# pcuCPU.net
KiCad netlist of a schematic drawn in Altium Designer
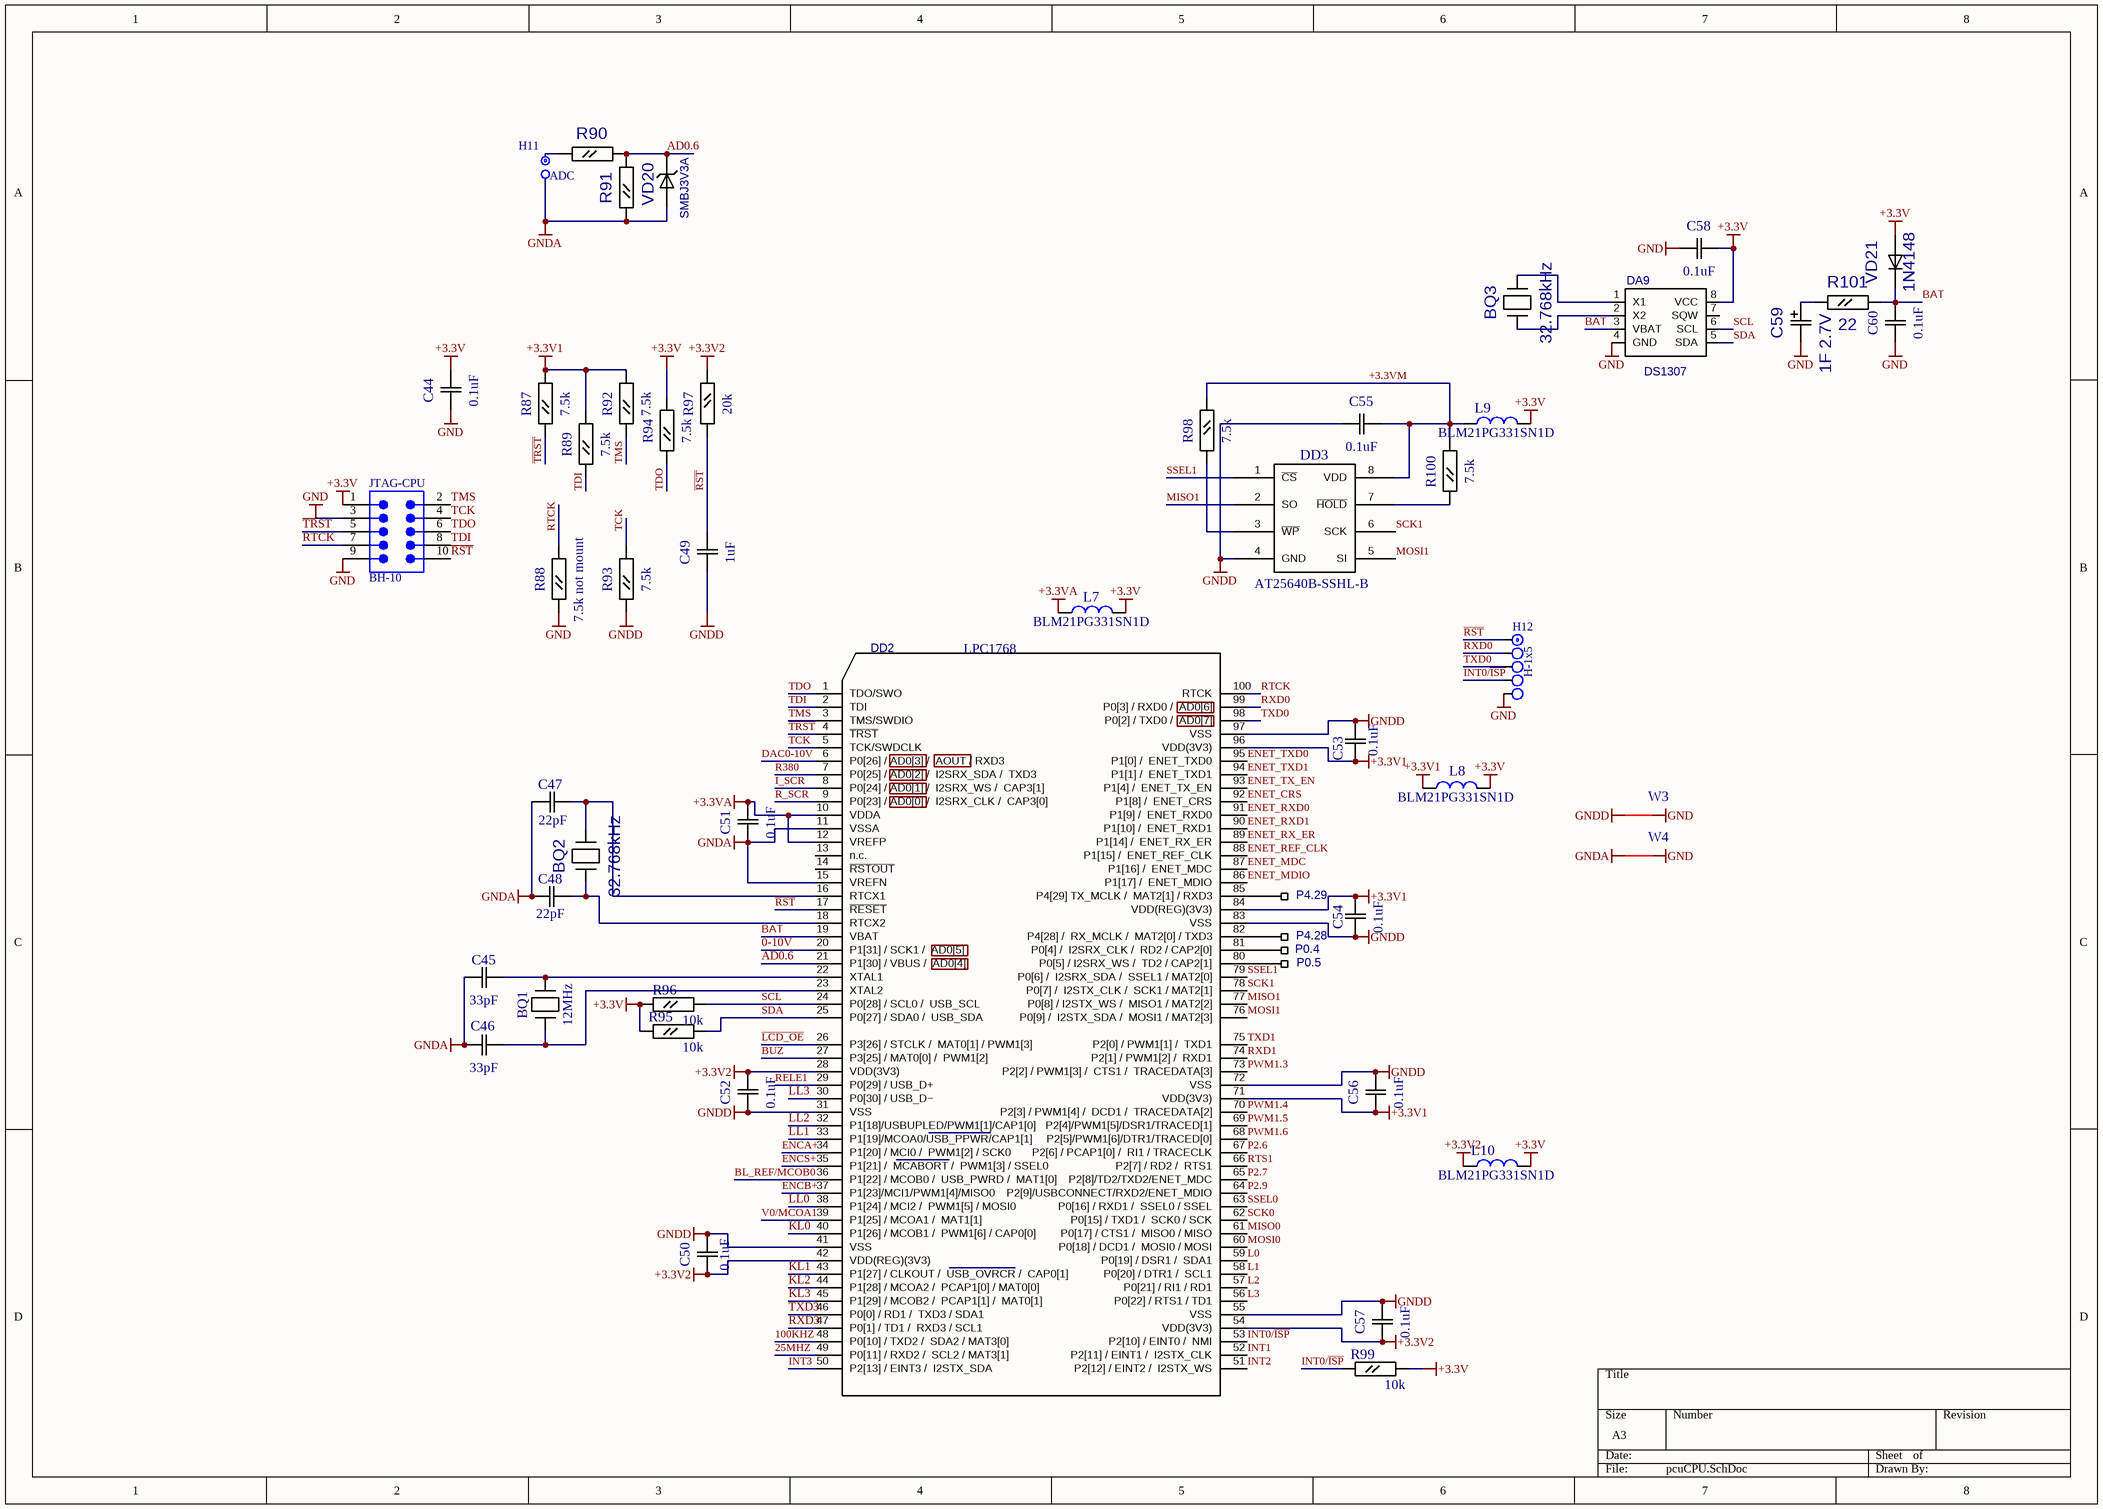
[diagram p0: pcuCPU.SchDoc]

(export (version "E")
  (design (tool "Eeschema 10.0.6"))
  (components
    (comp (ref "BQ1")
      (value "12MHz")
      (footprint "FurmansLib:HC49U")
      (description "HC49_VH")
      (libsource (lib "Furmans") (part "HC49_VH"))
    )
    (comp (ref "BQ2")
      (value "32.768kHz")
      (footprint "Furmans:R26")
      (description "R26")
      (libsource (lib "Furmans") (part "R26"))
    )
    (comp (ref "BQ3")
      (value "32.768kHz")
      (footprint "FurmansLib:R26smd")
      (description "R26")
      (libsource (lib "Furmans") (part "R26"))
    )
    (comp (ref "C44")
      (value "0.1uF")
      (footprint "FurmansLib:C0805")
      (description "C0805")
      (libsource (lib "FurmansLib") (part "C0805"))
    )
    (comp (ref "C45")
      (value "33pF")
      (footprint "FurmansLib:C0805")
      (description "C0805")
      (libsource (lib "FurmansLib") (part "C0805"))
    )
    (comp (ref "C46")
      (value "33pF")
      (footprint "FurmansLib:C0805")
      (description "C0805")
      (libsource (lib "FurmansLib") (part "C0805"))
    )
    (comp (ref "C47")
      (value "22pF")
      (footprint "FurmansLib:C0805")
      (description "C0805")
      (libsource (lib "FurmansLib") (part "C0805"))
    )
    (comp (ref "C48")
      (value "22pF")
      (footprint "FurmansLib:C0805")
      (description "C0805")
      (libsource (lib "FurmansLib") (part "C0805"))
    )
    (comp (ref "C49")
      (value "1uF")
      (footprint "FurmansLib:C0805")
      (description "C0805")
      (libsource (lib "FurmansLib") (part "C0805"))
    )
    (comp (ref "C50")
      (value "0.1uF")
      (footprint "FurmansLib:C0805")
      (description "C0805")
      (libsource (lib "FurmansLib") (part "C0805"))
    )
    (comp (ref "C51")
      (value "0.1uF")
      (footprint "FurmansLib:C0805")
      (description "C0805")
      (libsource (lib "FurmansLib") (part "C0805"))
    )
    (comp (ref "C52")
      (value "0.1uF")
      (footprint "FurmansLib:C0805")
      (description "C0805")
      (libsource (lib "FurmansLib") (part "C0805"))
    )
    (comp (ref "C53")
      (value "0.1uF")
      (footprint "FurmansLib:C0805")
      (description "C0805")
      (libsource (lib "FurmansLib") (part "C0805"))
    )
    (comp (ref "C54")
      (value "0.1uF")
      (footprint "FurmansLib:C0805")
      (description "C0805")
      (libsource (lib "FurmansLib") (part "C0805"))
    )
    (comp (ref "C55")
      (value "0.1uF")
      (footprint "FurmansLib:C0805")
      (description "C0805")
      (libsource (lib "FurmansLib") (part "C0805"))
    )
    (comp (ref "C56")
      (value "0.1uF")
      (footprint "FurmansLib:C0805")
      (description "C0805")
      (libsource (lib "FurmansLib") (part "C0805"))
    )
    (comp (ref "C57")
      (value "0.1uF")
      (footprint "FurmansLib:C0805")
      (description "C0805")
      (libsource (lib "FurmansLib") (part "C0805"))
    )
    (comp (ref "C58")
      (value "0.1uF")
      (footprint "FurmansLib:C0805")
      (description "C0805")
      (libsource (lib "FurmansLib") (part "C0805"))
    )
    (comp (ref "C59")
      (value "1F 2.7V")
      (footprint "El-d8-h12-F3.81")
      (description "Cap El")
      (libsource (lib "FurmansLib") (part "Cap El"))
    )
    (comp (ref "C60")
      (value "0.1uF")
      (footprint "FurmansLib:C0805")
      (description "C0805")
      (libsource (lib "FurmansLib") (part "C0805"))
    )
    (comp (ref "DA9") (value "DS1307") (footprint "SO8-1.27") (libsource (lib "FurmansLib") (part "DS1307")))
    (comp (ref "DD2")
      (value "LPC1768")
      (footprint "QFP100-0.5MM")
      (libsource (lib "Furmans") (part "LPC176_"))
    )
    (comp (ref "DD3")
      (value "AT25640B-SSHL-B")
      (footprint "FurmansLib:SO8-150")
      (description "FM25L16-G")
      (libsource (lib "*") (part "FM25L16-G"))
    )
    (comp (ref "H11") (value "ADC") (footprint "J1x2") (libsource (lib "FurmansLib") (part "H-1x2")))
    (comp (ref "H12")
      (value "H-1x5")
      (footprint "FurmansLib:J1x5")
      (libsource (lib "FurmansLib") (part "H-1x5"))
    )
    (comp (ref "JTAG-CPU")
      (value "BH-10")
      (footprint "FurmansLib:J2x5")
      (description "Flat Cable Connector (IDC), PCB Transition Connector, 2 Rows, Solder Pin, 10 Contacts")
      (fields (field (name "PUBLISHER") "Altium Limited"))
      (libsource (lib "FurmansLib") (part "BH-10"))
    )
    (comp (ref "L7")
      (value "BLM21PG331SN1D")
      (footprint "R0805")
      (description "Ferrite beads")
      (libsource (lib "FurmansLib") (part "BLM21PG331SN1D"))
    )
    (comp (ref "L8")
      (value "BLM21PG331SN1D")
      (footprint "R0805")
      (description "Ferrite beads")
      (libsource (lib "FurmansLib") (part "BLM21PG331SN1D"))
    )
    (comp (ref "L9")
      (value "BLM21PG331SN1D")
      (footprint "R0805")
      (description "Ferrite beads")
      (libsource (lib "FurmansLib") (part "BLM21PG331SN1D"))
    )
    (comp (ref "L10")
      (value "BLM21PG331SN1D")
      (footprint "R0805")
      (description "Ferrite beads")
      (libsource (lib "FurmansLib") (part "BLM21PG331SN1D"))
    )
    (comp (ref "P0.4")
      (value "PCB_1R")
      (footprint "PCB_1R_Oval")
      (libsource (lib "FurmansLib") (part "PCB_1R"))
    )
    (comp (ref "P0.5")
      (value "PCB_1R")
      (footprint "PCB_1R_Oval")
      (libsource (lib "FurmansLib") (part "PCB_1R"))
    )
    (comp (ref "P4.28")
      (value "PCB_1R")
      (footprint "PCB_1R_Oval")
      (libsource (lib "FurmansLib") (part "PCB_1R"))
    )
    (comp (ref "P4.29")
      (value "PCB_1R")
      (footprint "PCB_1R_Oval")
      (libsource (lib "FurmansLib") (part "PCB_1R"))
    )
    (comp (ref "R87")
      (value "7.5k")
      (footprint "R0805")
      (description "R0805")
      (libsource (lib "*") (part "R0805"))
    )
    (comp (ref "R88")
      (value "7.5k not mount")
      (footprint "R0805")
      (description "R0805")
      (libsource (lib "*") (part "R0805"))
    )
    (comp (ref "R89")
      (value "7.5k")
      (footprint "R0805")
      (description "R0805")
      (libsource (lib "*") (part "R0805"))
    )
    (comp (ref "R90") (value "R0805") (footprint "R0805") (libsource (lib "FurmansLib") (part "R0805")))
    (comp (ref "R91") (value "R0805") (footprint "R0805") (libsource (lib "FurmansLib") (part "R0805")))
    (comp (ref "R92")
      (value "7.5k")
      (footprint "R0805")
      (description "R0805")
      (libsource (lib "*") (part "R0805"))
    )
    (comp (ref "R93")
      (value "7.5k")
      (footprint "R0805")
      (description "R0805")
      (libsource (lib "*") (part "R0805"))
    )
    (comp (ref "R94")
      (value "7.5k")
      (footprint "R0805")
      (description "R0805")
      (libsource (lib "*") (part "R0805"))
    )
    (comp (ref "R95")
      (value "10k")
      (footprint "R0805")
      (description "R0805")
      (libsource (lib "FurmansLib") (part "R0805"))
    )
    (comp (ref "R96")
      (value "10k")
      (footprint "R0805")
      (description "R0805")
      (libsource (lib "FurmansLib") (part "R0805"))
    )
    (comp (ref "R97")
      (value "20k")
      (footprint "R0805")
      (description "R0805")
      (libsource (lib "*") (part "R0805"))
    )
    (comp (ref "R98")
      (value "7.5k")
      (footprint "R0805")
      (description "R0805")
      (libsource (lib "*") (part "R0805"))
    )
    (comp (ref "R99")
      (value "10k")
      (footprint "R0805")
      (description "R0805")
      (libsource (lib "FurmansLib") (part "R0805"))
    )
    (comp (ref "R100")
      (value "7.5k")
      (footprint "R0805")
      (description "R0805")
      (libsource (lib "*") (part "R0805"))
    )
    (comp (ref "R101")
      (value "22")
      (footprint "R0805")
      (description "R0805")
      (libsource (lib "FurmansLib") (part "R0805"))
    )
    (comp (ref "VD20")
      (value "SMBJ3V3A")
      (footprint "DO-214AA(SMB)")
      (description "10BQ100")
      (libsource (lib "FurmansLib") (part "10BQ100"))
    )
    (comp (ref "VD21")
      (value "1N4148")
      (footprint "SOD123")
      (description "DIOD 1N4148")
      (fields (field (name "Comment") "DIOD_thin"))
      (libsource (lib "FurmansLib") (part "DIOD_thin"))
    )
    (comp (ref "W3")
      (value "Net connector")
      (footprint "FurmansLib:Net connector")
      (description "NET CONNECTOR")
      (libsource (lib "Furmans") (part "Net connector"))
    )
    (comp (ref "W4")
      (value "Net connector")
      (footprint "FurmansLib:Net connector0.5mm")
      (description "NET CONNECTOR")
      (libsource (lib "Furmans") (part "Net connector"))
    )
  )
  (nets
    (net (code "1") (name "+3.3V") (class "Default")
      (node (ref "C44") (pin "2") (pintype "passive"))
      (node (ref "C58") (pin "1") (pintype "passive"))
      (node (ref "DA9") (pin "8") (pinfunction "VCC_8") (pintype "passive"))
      (node (ref "JTAG-CPU") (pin "1") (pinfunction "1_1") (pintype "passive"))
      (node (ref "L10") (pin "2") (pintype "passive"))
      (node (ref "L7") (pin "2") (pintype "passive"))
      (node (ref "L8") (pin "2") (pintype "passive"))
      (node (ref "L9") (pin "2") (pintype "passive"))
      (node (ref "R94") (pin "1") (pintype "passive"))
      (node (ref "R95") (pin "2") (pintype "passive"))
      (node (ref "R96") (pin "2") (pintype "passive"))
      (node (ref "R99") (pin "1") (pintype "passive"))
      (node (ref "VD21") (pin "2") (pinfunction "+_2") (pintype "passive"))
    )
    (net (code "2") (name "+3.3V1") (class "Default")
      (node (ref "C53") (pin "2") (pintype "passive"))
      (node (ref "C54") (pin "2") (pintype "passive"))
      (node (ref "C56") (pin "2") (pintype "passive"))
      (node (ref "DD2") (pin "71") (pinfunction "VDD(3V3)_71") (pintype "passive"))
      (node (ref "DD2") (pin "84") (pinfunction "VDD(REG)(3V3)_84") (pintype "passive"))
      (node (ref "DD2") (pin "96") (pinfunction "VDD(3V3)_96") (pintype "passive"))
      (node (ref "L8") (pin "1") (pintype "passive"))
      (node (ref "R87") (pin "1") (pintype "passive"))
      (node (ref "R89") (pin "1") (pintype "passive"))
      (node (ref "R92") (pin "1") (pintype "passive"))
    )
    (net (code "3") (name "+3.3V2") (class "Default")
      (node (ref "C50") (pin "2") (pintype "passive"))
      (node (ref "C52") (pin "2") (pintype "passive"))
      (node (ref "C57") (pin "2") (pintype "passive"))
      (node (ref "DD2") (pin "28") (pinfunction "VDD(3V3)_28") (pintype "passive"))
      (node (ref "DD2") (pin "42") (pinfunction "VDD(REG)(3V3)_42") (pintype "passive"))
      (node (ref "DD2") (pin "54") (pinfunction "VDD(3V3)_54") (pintype "passive"))
      (node (ref "L10") (pin "1") (pintype "passive"))
      (node (ref "R97") (pin "2") (pintype "passive"))
    )
    (net (code "4") (name "+3.3VA") (class "Default")
      (node (ref "C51") (pin "2") (pintype "passive"))
      (node (ref "DD2") (pin "10") (pinfunction "VDDA_10") (pintype "passive"))
      (node (ref "DD2") (pin "12") (pinfunction "VREFP_12") (pintype "passive"))
      (node (ref "L7") (pin "1") (pintype "passive"))
    )
    (net (code "5") (name "/+3.3VM") (class "Default")
      (node (ref "C55") (pin "1") (pintype "passive"))
      (node (ref "DD3") (pin "8") (pinfunction "VDD_8") (pintype "passive"))
      (node (ref "L9") (pin "1") (pintype "passive"))
      (node (ref "R100") (pin "1") (pintype "passive"))
      (node (ref "R98") (pin "2") (pintype "passive"))
    )
    (net (code "6") (name "/0-10V") (class "Default")
      (node (ref "DD2") (pin "20") (pinfunction "P1[31]_/_SCK1_/__AD0[5]_20") (pintype "passive"))
    )
    (net (code "7") (name "/25MHZ") (class "Default")
      (node (ref "DD2") (pin "49") (pinfunction "P0[11]_/_RXD2_/__SCL2_/_MAT3[1]_49") (pintype "passive"))
    )
    (net (code "8") (name "/100KHZ") (class "Default")
      (node (ref "DD2") (pin "48") (pinfunction "P0[10]_/_TXD2_/__SDA2_/_MAT3[0]_48") (pintype "passive"))
    )
    (net (code "9") (name "/AD0.6") (class "Default")
      (node (ref "DD2") (pin "21") (pinfunction "P1[30]_/_VBUS_/__AD0[4]_21") (pintype "passive"))
      (node (ref "R90") (pin "1") (pintype "passive"))
      (node (ref "R91") (pin "1") (pintype "passive"))
      (node (ref "VD20") (pin "1") (pintype "passive"))
    )
    (net (code "10") (name "/BAT") (class "Default")
      (node (ref "C60") (pin "1") (pintype "passive"))
      (node (ref "DA9") (pin "3") (pinfunction "VBAT_3") (pintype "passive"))
      (node (ref "DD2") (pin "19") (pinfunction "VBAT_19") (pintype "passive"))
      (node (ref "R101") (pin "1") (pintype "passive"))
      (node (ref "VD21") (pin "1") (pinfunction "-_1") (pintype "passive"))
    )
    (net (code "11") (name "/BL_REF{slash}MCOB0") (class "Default")
      (node (ref "DD2") (pin "36") (pinfunction "P1[22]_/_MCOB0_/__USB_PWRD_/__MAT1[0]_36") (pintype "passive"))
    )
    (net (code "12") (name "/BUZ") (class "Default")
      (node (ref "DD2") (pin "27") (pinfunction "P3[25]_/_MAT0[0]_/__PWM1[2]_27") (pintype "passive"))
    )
    (net (code "13") (name "/DAC0-10V") (class "Default")
      (node (ref "DD2") (pin "6") (pinfunction "P0[26]_/_AD0[3]_/__AOUT_/_RXD3_6") (pintype "passive"))
    )
    (net (code "14") (name "/ENCA+") (class "Default")
      (node (ref "DD2") (pin "34") (pinfunction "P1[20]_/_MCI0_/__PWM1[2]_/_SCK0_34") (pintype "passive"))
    )
    (net (code "15") (name "/ENCB+") (class "Default")
      (node (ref "DD2") (pin "37") (pinfunction "P1[23]/MCI1/PWM1[4]/MISO0_37") (pintype "passive"))
    )
    (net (code "16") (name "/ENCS+") (class "Default")
      (node (ref "DD2") (pin "35") (pinfunction "P1[21]_/__MCABORT_/__PWM1[3]_/_SSEL0_35") (pintype "passive"))
    )
    (net (code "17") (name "/ENET_CRS") (class "Default")
      (node (ref "DD2") (pin "92") (pinfunction "P1[8]_/__ENET_CRS_92") (pintype "passive"))
    )
    (net (code "18") (name "/ENET_MDC") (class "Default")
      (node (ref "DD2") (pin "87") (pinfunction "P1[16]_/__ENET_MDC_87") (pintype "passive"))
    )
    (net (code "19") (name "/ENET_MDIO") (class "Default")
      (node (ref "DD2") (pin "86") (pinfunction "P1[17]_/__ENET_MDIO_86") (pintype "passive"))
    )
    (net (code "20") (name "/ENET_REF_CLK") (class "Default")
      (node (ref "DD2") (pin "88") (pinfunction "P1[15]_/__ENET_REF_CLK_88") (pintype "passive"))
    )
    (net (code "21") (name "/ENET_RXD0") (class "Default")
      (node (ref "DD2") (pin "91") (pinfunction "P1[9]_/__ENET_RXD0_91") (pintype "passive"))
    )
    (net (code "22") (name "/ENET_RXD1") (class "Default")
      (node (ref "DD2") (pin "90") (pinfunction "P1[10]_/__ENET_RXD1_90") (pintype "passive"))
    )
    (net (code "23") (name "/ENET_RX_ER") (class "Default")
      (node (ref "DD2") (pin "89") (pinfunction "P1[14]_/__ENET_RX_ER_89") (pintype "passive"))
    )
    (net (code "24") (name "/ENET_TXD0") (class "Default")
      (node (ref "DD2") (pin "95") (pinfunction "P1[0]_/__ENET_TXD0_95") (pintype "passive"))
    )
    (net (code "25") (name "/ENET_TXD1") (class "Default")
      (node (ref "DD2") (pin "94") (pinfunction "P1[1]_/__ENET_TXD1_94") (pintype "passive"))
    )
    (net (code "26") (name "/ENET_TX_EN") (class "Default")
      (node (ref "DD2") (pin "93") (pinfunction "P1[4]_/__ENET_TX_EN_93") (pintype "passive"))
    )
    (net (code "27") (name "/INT0{slash}~{ISP}") (class "Default")
      (node (ref "DD2") (pin "53") (pinfunction "P2[10]_/_EINT0_/__NMI_53") (pintype "passive"))
      (node (ref "H12") (pin "4") (pinfunction "4_4") (pintype "passive"))
      (node (ref "R99") (pin "2") (pintype "passive"))
    )
    (net (code "28") (name "/INT1") (class "Default")
      (node (ref "DD2") (pin "52") (pinfunction "P2[11]_/_EINT1_/__I2STX_CLK_52") (pintype "passive"))
    )
    (net (code "29") (name "/INT2") (class "Default")
      (node (ref "DD2") (pin "51") (pinfunction "P2[12]_/_EINT2_/__I2STX_WS_51") (pintype "passive"))
    )
    (net (code "30") (name "/INT3") (class "Default")
      (node (ref "DD2") (pin "50") (pinfunction "P2[13]_/_EINT3_/__I2STX_SDA_50") (pintype "passive"))
    )
    (net (code "31") (name "/I_SCR") (class "Default")
      (node (ref "DD2") (pin "8") (pinfunction "P0[24]_/_AD0[1]_/__I2SRX_WS_/__CAP3[1]_8") (pintype "passive"))
    )
    (net (code "32") (name "/KL0") (class "Default")
      (node (ref "DD2") (pin "40") (pinfunction "P1[26]_/_MCOB1_/__PWM1[6]_/_CAP0[0]_40") (pintype "passive"))
    )
    (net (code "33") (name "/KL1") (class "Default")
      (node (ref "DD2") (pin "43") (pinfunction "P1[27]_/_CLKOUT_/__USB_OVRCR_/__CAP0[1]_43") (pintype "passive"))
    )
    (net (code "34") (name "/KL2") (class "Default")
      (node (ref "DD2") (pin "44") (pinfunction "P1[28]_/_MCOA2_/__PCAP1[0]_/_MAT0[0]_44") (pintype "passive"))
    )
    (net (code "35") (name "/KL3") (class "Default")
      (node (ref "DD2") (pin "45") (pinfunction "P1[29]_/_MCOB2_/__PCAP1[1]_/__MAT0[1]_45") (pintype "passive"))
    )
    (net (code "36") (name "/L0") (class "Default")
      (node (ref "DD2") (pin "59") (pinfunction "P0[19]_/_DSR1_/__SDA1_59") (pintype "passive"))
    )
    (net (code "37") (name "/L1") (class "Default")
      (node (ref "DD2") (pin "58") (pinfunction "P0[20]_/_DTR1_/__SCL1_58") (pintype "passive"))
    )
    (net (code "38") (name "/L2") (class "Default")
      (node (ref "DD2") (pin "57") (pinfunction "P0[21]_/_RI1_/_RD1_57") (pintype "passive"))
    )
    (net (code "39") (name "/L3") (class "Default")
      (node (ref "DD2") (pin "56") (pinfunction "P0[22]_/_RTS1_/_TD1_56") (pintype "passive"))
    )
    (net (code "40") (name "/LCD_OE") (class "Default")
      (node (ref "DD2") (pin "26") (pinfunction "P3[26]_/_STCLK_/__MAT0[1]_/_PWM1[3]_26") (pintype "passive"))
    )
    (net (code "41") (name "/LL0") (class "Default")
      (node (ref "DD2") (pin "38") (pinfunction "P1[24]_/_MCI2_/__PWM1[5]_/_MOSI0_38") (pintype "passive"))
    )
    (net (code "42") (name "/LL1") (class "Default")
      (node (ref "DD2") (pin "33") (pinfunction "P1[19]/MCOA0/USB_PPWR/CAP1[1]_33") (pintype "passive"))
    )
    (net (code "43") (name "/LL2") (class "Default")
      (node (ref "DD2") (pin "32") (pinfunction "P1[18]/USBUPLED/PWM1[1]/CAP1[0]_32") (pintype "passive"))
    )
    (net (code "44") (name "/LL3") (class "Default")
      (node (ref "DD2") (pin "30") (pinfunction "P0[30]_/_USB_D−_30") (pintype "passive"))
    )
    (net (code "45") (name "/MISO0") (class "Default")
      (node (ref "DD2") (pin "61") (pinfunction "P0[17]_/_CTS1_/__MISO0_/_MISO_61") (pintype "passive"))
    )
    (net (code "46") (name "/MISO1") (class "Default")
      (node (ref "DD2") (pin "77") (pinfunction "P0[8]_/_I2STX_WS_/__MISO1_/_MAT2[2]_77") (pintype "passive"))
      (node (ref "DD3") (pin "2") (pinfunction "SO_2") (pintype "passive"))
    )
    (net (code "47") (name "/MOSI0") (class "Default")
      (node (ref "DD2") (pin "60") (pinfunction "P0[18]_/_DCD1_/__MOSI0_/_MOSI_60") (pintype "passive"))
    )
    (net (code "48") (name "/MOSI1") (class "Default")
      (node (ref "DD2") (pin "76") (pinfunction "P0[9]_/__I2STX_SDA_/__MOSI1_/_MAT2[3]_76") (pintype "passive"))
      (node (ref "DD3") (pin "5") (pinfunction "SI_5") (pintype "passive"))
    )
    (net (code "49") (name "/P2.6") (class "Default")
      (node (ref "DD2") (pin "67") (pinfunction "P2[6]_/_PCAP1[0]_/__RI1_/_TRACECLK_67") (pintype "passive"))
    )
    (net (code "50") (name "/P2.7") (class "Default")
      (node (ref "DD2") (pin "65") (pinfunction "P2[8]/TD2/TXD2/ENET_MDC_65") (pintype "passive"))
    )
    (net (code "51") (name "/P2.9") (class "Default")
      (node (ref "DD2") (pin "64") (pinfunction "P2[9]/USBCONNECT/RXD2/ENET_MDIO_64") (pintype "passive"))
    )
    (net (code "52") (name "/PWM1.3") (class "Default")
      (node (ref "DD2") (pin "73") (pinfunction "P2[2]_/_PWM1[3]_/__CTS1_/__TRACEDATA[3]_73") (pintype "passive"))
    )
    (net (code "53") (name "/PWM1.4") (class "Default")
      (node (ref "DD2") (pin "70") (pinfunction "P2[3]_/_PWM1[4]_/__DCD1_/__TRACEDATA[2]_70") (pintype "passive"))
    )
    (net (code "54") (name "/PWM1.5") (class "Default")
      (node (ref "DD2") (pin "69") (pinfunction "P2[4]/PWM1[5]/DSR1/TRACED[1]_69") (pintype "passive"))
    )
    (net (code "55") (name "/PWM1.6") (class "Default")
      (node (ref "DD2") (pin "68") (pinfunction "P2[5]/PWM1[6]/DTR1/TRACED[0]_68") (pintype "passive"))
    )
    (net (code "56") (name "/R380") (class "Default")
      (node (ref "DD2") (pin "7") (pinfunction "P0[25]_/_AD0[2]_/__I2SRX_SDA_/__TXD3_7") (pintype "passive"))
    )
    (net (code "57") (name "/RELE1") (class "Default")
      (node (ref "DD2") (pin "29") (pinfunction "P0[29]_/_USB_D+_29") (pintype "passive"))
    )
    (net (code "58") (name "/RTCK") (class "Default")
      (node (ref "DD2") (pin "100") (pinfunction "RTCK_100") (pintype "passive"))
      (node (ref "JTAG-CPU") (pin "7") (pinfunction "7_7") (pintype "passive"))
      (node (ref "R88") (pin "1") (pintype "passive"))
    )
    (net (code "59") (name "/RTS1") (class "Default")
      (node (ref "DD2") (pin "66") (pinfunction "P2[7]_/_RD2_/__RTS1_66") (pintype "passive"))
    )
    (net (code "60") (name "/RXD0") (class "Default")
      (node (ref "DD2") (pin "99") (pinfunction "P0[3]_/_RXD0_/__AD0[6]_99") (pintype "passive"))
      (node (ref "H12") (pin "2") (pinfunction "2_2") (pintype "passive"))
    )
    (net (code "61") (name "/RXD1") (class "Default")
      (node (ref "DD2") (pin "74") (pinfunction "P2[1]_/_PWM1[2]_/__RXD1_74") (pintype "passive"))
    )
    (net (code "62") (name "/RXD3") (class "Default")
      (node (ref "DD2") (pin "47") (pinfunction "P0[1]_/_TD1_/__RXD3_/_SCL1_47") (pintype "passive"))
    )
    (net (code "63") (name "/R_SCR") (class "Default")
      (node (ref "DD2") (pin "9") (pinfunction "P0[23]_/_AD0[0]_/__I2SRX_CLK_/__CAP3[0]_9") (pintype "passive"))
    )
    (net (code "64") (name "/SCK0") (class "Default")
      (node (ref "DD2") (pin "62") (pinfunction "P0[15]_/_TXD1_/__SCK0_/_SCK_62") (pintype "passive"))
    )
    (net (code "65") (name "/SCK1") (class "Default")
      (node (ref "DD2") (pin "78") (pinfunction "P0[7]_/__I2STX_CLK_/__SCK1_/_MAT2[1]_78") (pintype "passive"))
      (node (ref "DD3") (pin "6") (pinfunction "SCK_6") (pintype "passive"))
    )
    (net (code "66") (name "/SCL") (class "Default")
      (node (ref "DA9") (pin "6") (pinfunction "SCL_6") (pintype "passive"))
      (node (ref "DD2") (pin "24") (pinfunction "P0[28]_/_SCL0_/__USB_SCL_24") (pintype "passive"))
      (node (ref "R96") (pin "1") (pintype "passive"))
    )
    (net (code "67") (name "/SDA") (class "Default")
      (node (ref "DA9") (pin "5") (pinfunction "SDA_5") (pintype "passive"))
      (node (ref "DD2") (pin "25") (pinfunction "P0[27]_/_SDA0_/__USB_SDA_25") (pintype "passive"))
      (node (ref "R95") (pin "1") (pintype "passive"))
    )
    (net (code "68") (name "/SSEL0") (class "Default")
      (node (ref "DD2") (pin "63") (pinfunction "P0[16]_/_RXD1_/__SSEL0_/_SSEL_63") (pintype "passive"))
    )
    (net (code "69") (name "/SSEL1") (class "Default")
      (node (ref "DD2") (pin "79") (pinfunction "P0[6]_/__I2SRX_SDA_/__SSEL1_/_MAT2[0]_79") (pintype "passive"))
      (node (ref "DD3") (pin "1") (pinfunction "~{CS}_1") (pintype "passive"))
    )
    (net (code "70") (name "/TCK") (class "Default")
      (node (ref "DD2") (pin "5") (pinfunction "TCK/SWDCLK_5") (pintype "passive"))
      (node (ref "JTAG-CPU") (pin "4") (pinfunction "4_4") (pintype "passive"))
      (node (ref "R93") (pin "1") (pintype "passive"))
    )
    (net (code "71") (name "/TDI") (class "Default")
      (node (ref "DD2") (pin "2") (pinfunction "TDI_2") (pintype "passive"))
      (node (ref "JTAG-CPU") (pin "8") (pinfunction "8_8") (pintype "passive"))
      (node (ref "R89") (pin "2") (pintype "passive"))
    )
    (net (code "72") (name "/TDO") (class "Default")
      (node (ref "DD2") (pin "1") (pinfunction "TDO/SWO_1") (pintype "passive"))
      (node (ref "JTAG-CPU") (pin "6") (pinfunction "6_6") (pintype "passive"))
      (node (ref "R94") (pin "2") (pintype "passive"))
    )
    (net (code "73") (name "/TMS") (class "Default")
      (node (ref "DD2") (pin "3") (pinfunction "TMS/SWDIO_3") (pintype "passive"))
      (node (ref "JTAG-CPU") (pin "2") (pinfunction "2_2") (pintype "passive"))
      (node (ref "R92") (pin "2") (pintype "passive"))
    )
    (net (code "74") (name "/TRST") (class "Default")
      (node (ref "DD2") (pin "4") (pinfunction "~{TRST}_4") (pintype "passive"))
      (node (ref "JTAG-CPU") (pin "5") (pinfunction "5_5") (pintype "passive"))
      (node (ref "R87") (pin "2") (pintype "passive"))
    )
    (net (code "75") (name "/TXD0") (class "Default")
      (node (ref "DD2") (pin "98") (pinfunction "P0[2]_/_TXD0_/__AD0[7]_98") (pintype "passive"))
      (node (ref "H12") (pin "3") (pinfunction "3_3") (pintype "passive"))
    )
    (net (code "76") (name "/TXD1") (class "Default")
      (node (ref "DD2") (pin "75") (pinfunction "P2[0]_/_PWM1[1]_/__TXD1_75") (pintype "passive"))
    )
    (net (code "77") (name "/TXD3") (class "Default")
      (node (ref "DD2") (pin "46") (pinfunction "P0[0]_/_RD1_/__TXD3_/_SDA1_46") (pintype "passive"))
    )
    (net (code "78") (name "/V0{slash}MCOA1") (class "Default")
      (node (ref "DD2") (pin "39") (pinfunction "P1[25]_/_MCOA1_/__MAT1[1]_39") (pintype "passive"))
    )
    (net (code "79") (name "/~{RST}") (class "Default")
      (node (ref "C49") (pin "2") (pintype "passive"))
      (node (ref "DD2") (pin "17") (pinfunction "~{RESET}_17") (pintype "passive"))
      (node (ref "H12") (pin "1") (pinfunction "1_1") (pintype "passive"))
      (node (ref "JTAG-CPU") (pin "10") (pinfunction "10_10") (pintype "passive"))
      (node (ref "R97") (pin "1") (pintype "passive"))
    )
    (net (code "80") (name "GND") (class "Default")
      (node (ref "C44") (pin "1") (pintype "passive"))
      (node (ref "C58") (pin "2") (pintype "passive"))
      (node (ref "C59") (pin "2") (pintype "passive"))
      (node (ref "C60") (pin "2") (pintype "passive"))
      (node (ref "DA9") (pin "4") (pinfunction "GND_4") (pintype "passive"))
      (node (ref "H12") (pin "5") (pinfunction "5_5") (pintype "passive"))
      (node (ref "JTAG-CPU") (pin "3") (pinfunction "3_3") (pintype "passive"))
      (node (ref "JTAG-CPU") (pin "9") (pinfunction "9_9") (pintype "passive"))
      (node (ref "R88") (pin "2") (pintype "passive"))
      (node (ref "W3") (pin "1") (pintype "passive"))
      (node (ref "W4") (pin "1") (pintype "passive"))
    )
    (net (code "81") (name "GNDA") (class "Default")
      (node (ref "C45") (pin "2") (pintype "passive"))
      (node (ref "C46") (pin "2") (pintype "passive"))
      (node (ref "C47") (pin "1") (pintype "passive"))
      (node (ref "C48") (pin "2") (pintype "passive"))
      (node (ref "C51") (pin "1") (pintype "passive"))
      (node (ref "DD2") (pin "11") (pinfunction "VSSA_11") (pintype "passive"))
      (node (ref "DD2") (pin "15") (pinfunction "VREFN_15") (pintype "passive"))
      (node (ref "H11") (pin "2") (pinfunction "2_2") (pintype "passive"))
      (node (ref "R91") (pin "2") (pintype "passive"))
      (node (ref "VD20") (pin "2") (pintype "passive"))
      (node (ref "W4") (pin "2") (pintype "passive"))
    )
    (net (code "82") (name "GNDD") (class "Default")
      (node (ref "C49") (pin "1") (pintype "passive"))
      (node (ref "C50") (pin "1") (pintype "passive"))
      (node (ref "C52") (pin "1") (pintype "passive"))
      (node (ref "C53") (pin "1") (pintype "passive"))
      (node (ref "C54") (pin "1") (pintype "passive"))
      (node (ref "C55") (pin "2") (pintype "passive"))
      (node (ref "C56") (pin "1") (pintype "passive"))
      (node (ref "C57") (pin "1") (pintype "passive"))
      (node (ref "DD2") (pin "31") (pinfunction "VSS_31") (pintype "passive"))
      (node (ref "DD2") (pin "41") (pinfunction "VSS_41") (pintype "passive"))
      (node (ref "DD2") (pin "55") (pinfunction "VSS_55") (pintype "passive"))
      (node (ref "DD2") (pin "72") (pinfunction "VSS_72") (pintype "passive"))
      (node (ref "DD2") (pin "83") (pinfunction "VSS_83") (pintype "passive"))
      (node (ref "DD2") (pin "97") (pinfunction "VSS_97") (pintype "passive"))
      (node (ref "DD3") (pin "4") (pinfunction "GND_4") (pintype "passive"))
      (node (ref "R93") (pin "2") (pintype "passive"))
      (node (ref "W3") (pin "2") (pintype "passive"))
    )
    (net (code "83") (name "Net-(C59-Pad1)") (class "Default")
      (node (ref "C59") (pin "1") (pintype "passive"))
      (node (ref "R101") (pin "2") (pintype "passive"))
    )
    (net (code "84") (name "Net-(DA9-X1)") (class "Default")
      (node (ref "BQ3") (pin "2") (pintype "passive"))
      (node (ref "DA9") (pin "1") (pinfunction "X1_1") (pintype "passive"))
    )
    (net (code "85") (name "Net-(DA9-X2)") (class "Default")
      (node (ref "BQ3") (pin "1") (pintype "passive"))
      (node (ref "DA9") (pin "2") (pinfunction "X2_2") (pintype "passive"))
    )
    (net (code "86") (name "Net-(DD2-P0[4]_{slash}__I2SRX_CLK_{slash}__RD2_{slash}_CAP2[0])") (class "Default")
      (node (ref "DD2") (pin "81") (pinfunction "P0[4]_/__I2SRX_CLK_/__RD2_/_CAP2[0]_81") (pintype "passive"))
      (node (ref "P0.4") (pin "1") (pinfunction "1_1") (pintype "passive"))
    )
    (net (code "87") (name "Net-(DD2-P0[5]_{slash}_I2SRX_WS_{slash}__TD2_{slash}_CAP2[1])") (class "Default")
      (node (ref "DD2") (pin "80") (pinfunction "P0[5]_/_I2SRX_WS_/__TD2_/_CAP2[1]_80") (pintype "passive"))
      (node (ref "P0.5") (pin "1") (pinfunction "1_1") (pintype "passive"))
    )
    (net (code "88") (name "Net-(DD2-P4[28]_{slash}__RX_MCLK_{slash}__MAT2[0]_{slash}_TXD3)") (class "Default")
      (node (ref "DD2") (pin "82") (pinfunction "P4[28]_/__RX_MCLK_/__MAT2[0]_/_TXD3_82") (pintype "passive"))
      (node (ref "P4.28") (pin "1") (pinfunction "1_1") (pintype "passive"))
    )
    (net (code "89") (name "Net-(DD2-P4[29]_TX_MCLK_{slash}__MAT2[1]_{slash}_RXD3)") (class "Default")
      (node (ref "DD2") (pin "85") (pinfunction "P4[29]_TX_MCLK_/__MAT2[1]_/_RXD3_85") (pintype "passive"))
      (node (ref "P4.29") (pin "1") (pinfunction "1_1") (pintype "passive"))
    )
    (net (code "90") (name "Net-(DD2-RTCX1)") (class "Default")
      (node (ref "BQ2") (pin "2") (pintype "passive"))
      (node (ref "C47") (pin "2") (pintype "passive"))
      (node (ref "DD2") (pin "16") (pinfunction "RTCX1_16") (pintype "passive"))
    )
    (net (code "91") (name "Net-(DD2-RTCX2)") (class "Default")
      (node (ref "BQ2") (pin "1") (pintype "passive"))
      (node (ref "C48") (pin "1") (pintype "passive"))
      (node (ref "DD2") (pin "18") (pinfunction "RTCX2_18") (pintype "passive"))
    )
    (net (code "92") (name "Net-(DD2-XTAL1)") (class "Default")
      (node (ref "BQ1") (pin "1") (pintype "passive"))
      (node (ref "C45") (pin "1") (pintype "passive"))
      (node (ref "DD2") (pin "22") (pinfunction "XTAL1_22") (pintype "passive"))
    )
    (net (code "93") (name "Net-(DD2-XTAL2)") (class "Default")
      (node (ref "BQ1") (pin "2") (pintype "passive"))
      (node (ref "C46") (pin "1") (pintype "passive"))
      (node (ref "DD2") (pin "23") (pinfunction "XTAL2_23") (pintype "passive"))
    )
    (net (code "94") (name "Net-(DD3-~{HOLD})") (class "Default")
      (node (ref "DD3") (pin "7") (pinfunction "~{HOLD}_7") (pintype "passive"))
      (node (ref "R100") (pin "2") (pintype "passive"))
    )
    (net (code "95") (name "Net-(DD3-~{WP})") (class "Default")
      (node (ref "DD3") (pin "3") (pinfunction "~{WP}_3") (pintype "passive"))
      (node (ref "R98") (pin "1") (pintype "passive"))
    )
    (net (code "96") (name "Net-(H11-Pad1)") (class "Default")
      (node (ref "H11") (pin "1") (pinfunction "1_1") (pintype "passive"))
      (node (ref "R90") (pin "2") (pintype "passive"))
    )
    (net (code "97") (name "unconnected-(DA9-SQW-Pad7)") (class "Default")
      (node (ref "DA9") (pin "7") (pinfunction "SQW_7") (pintype "passive"))
    )
    (net (code "98") (name "unconnected-(DD2-n.c.-Pad13)") (class "Default")
      (node (ref "DD2") (pin "13") (pinfunction "n.c._13") (pintype "passive"))
    )
    (net (code "99") (name "unconnected-(DD2-~{RSTOUT}-Pad14)") (class "Default")
      (node (ref "DD2") (pin "14") (pinfunction "~{RSTOUT}_14") (pintype "passive"))
    )
  )
)
